# Sheet2.net
KiCad netlist of a schematic drawn in Altium Designer
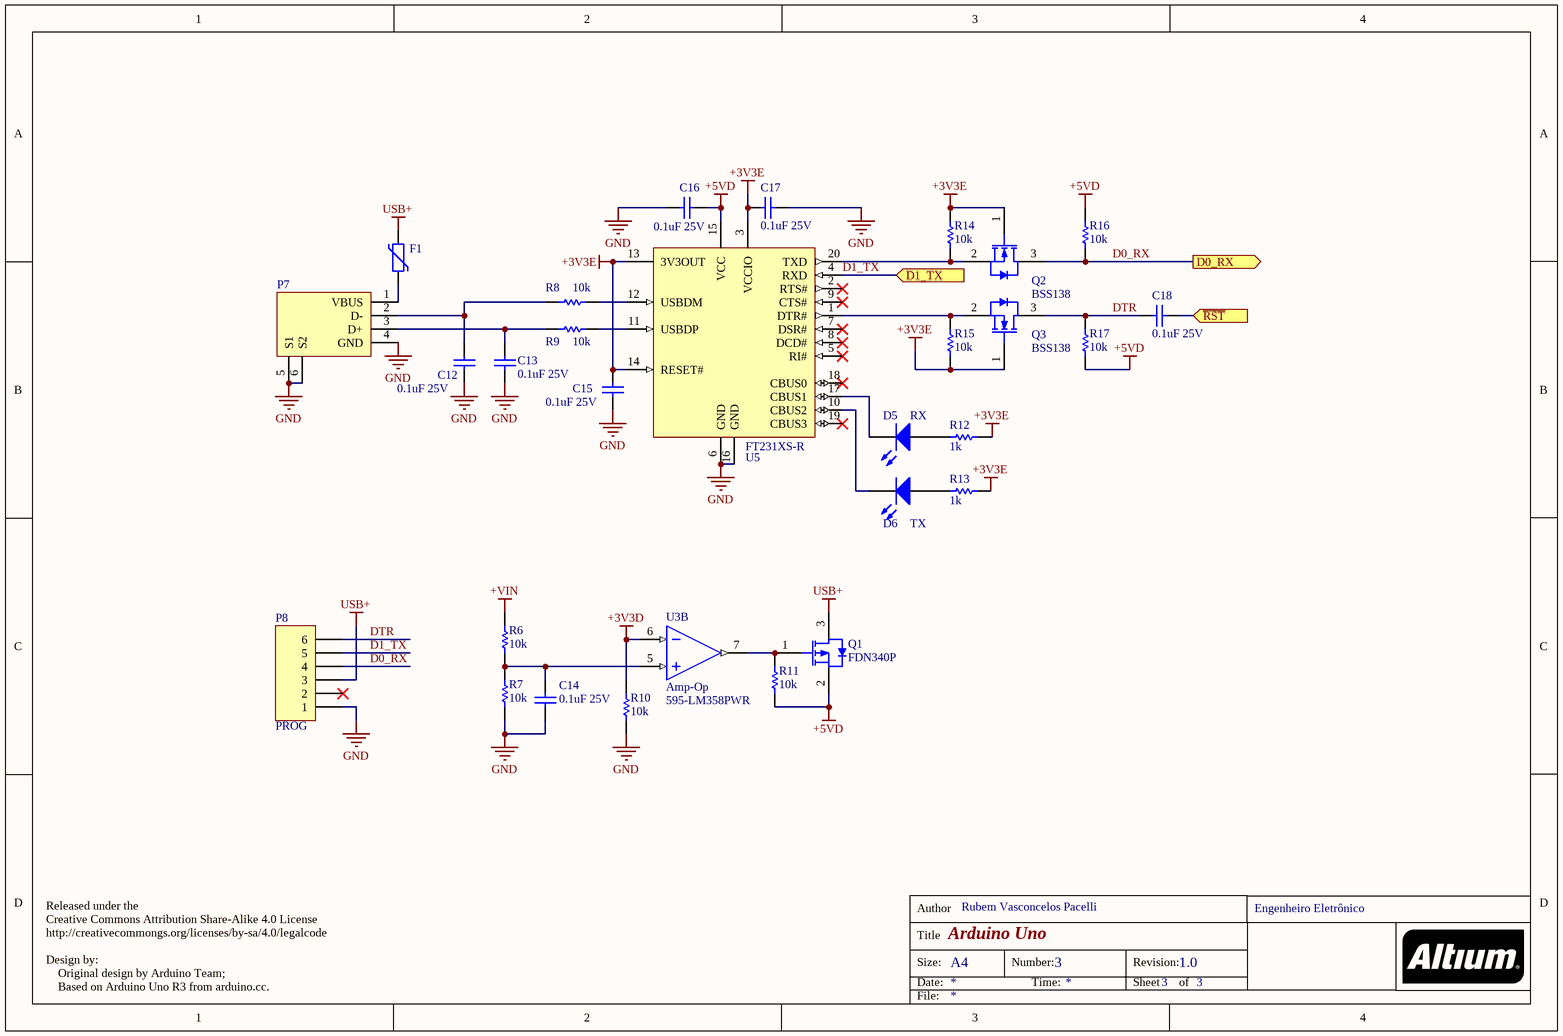
[diagram p0: Sheet2.SchDoc]

(export (version "E")
  (design (tool "Eeschema 10.0.6"))
  (components
    (comp (ref "C12")
      (value "0.1uF 25V")
      (footprint "C1608[0603]")
      (description "Capacitor Decoupling")
      (fields (field (name "MANUFACTURER PART NUMBER") "GCM188R71E104KA57D") (field (name "TOLERANCE") "10%"))
      (libsource (lib "Basic Library") (part "C"))
    )
    (comp (ref "C13")
      (value "0.1uF 25V")
      (footprint "C1608[0603]")
      (description "Capacitor Decoupling")
      (fields (field (name "MANUFACTURER PART NUMBER") "GCM188R71E104KA57D") (field (name "TOLERANCE") "10%"))
      (libsource (lib "Basic Library") (part "C"))
    )
    (comp (ref "C14")
      (value "0.1uF 25V")
      (footprint "C1608[0603]")
      (description "Decoupling Capacitor")
      (fields (field (name "MANUFACTURER PART NUMBER") "GCM188R71E104KA57D") (field (name "TOLERANCE") "10%"))
      (libsource (lib "Basic Library") (part "C"))
    )
    (comp (ref "C15")
      (value "0.1uF 25V")
      (footprint "C1608[0603]")
      (description "Capacitor Decoupling")
      (fields (field (name "MANUFACTURER PART NUMBER") "GCM188R71E104KA57D") (field (name "TOLERANCE") "10%"))
      (libsource (lib "Basic Library") (part "C"))
    )
    (comp (ref "C16")
      (value "0.1uF 25V")
      (footprint "C1608[0603]")
      (description "Capacitor Decoupling")
      (fields (field (name "MANUFACTURER PART NUMBER") "GCM188R71E104KA57D") (field (name "TOLERANCE") "10%"))
      (libsource (lib "Basic Library") (part "C"))
    )
    (comp (ref "C17")
      (value "0.1uF 25V")
      (footprint "C1608[0603]")
      (description "Capacitor Decoupling")
      (fields (field (name "MANUFACTURER PART NUMBER") "GCM188R71E104KA57D") (field (name "TOLERANCE") "10%"))
      (libsource (lib "Basic Library") (part "C"))
    )
    (comp (ref "C18")
      (value "0.1uF 25V")
      (footprint "C1608[0603]")
      (description "Capacitor Coupling")
      (fields (field (name "MANUFACTURER PART NUMBER") "GCM188R71E104KA57D") (field (name "TOLERANCE") "10%"))
      (libsource (lib "Basic Library") (part "C"))
    )
    (comp (ref "D5")
      (value "RX")
      (footprint "LED-0603-R")
      (description "LED visual indicator")
      (fields (field (name "MANUFACTURER PART NUMBER") "LTST-C190KSKT"))
      (libsource (lib "Basic Library") (part "LED"))
    )
    (comp (ref "D6")
      (value "TX")
      (footprint "LED-0603-R")
      (description "LED visual indicator")
      (fields (field (name "MANUFACTURER PART NUMBER") "LTST-C190KSKT"))
      (libsource (lib "Basic Library") (part "LED"))
    )
    (comp (ref "F1")
      (value "~")
      (footprint "MF-MSMF050")
      (description "Resettable Fuse")
      (fields (field (name "MANUFACTURER PART NUMBER") "MF-MSMF050-2"))
      (libsource (lib "Components Library") (part "MF-MSMF050-2"))
    )
    (comp (ref "P7")
      (value "~")
      (footprint "USBB1HSB6")
      (description "USB - B Receptacle")
      (fields
        (field (name "MANUFACTURER") "On-Shore Technology")
        (field (name "MANUFACTURER PART NUMBER") "USB-B1HSB6")
      )
      (libsource (lib "Connectors Library") (part "USB-B1HSB6"))
    )
    (comp (ref "P8")
      (value "PROG")
      (footprint "HDR1X6m")
      (description "Header, 6-Pin")
      (fields
        (field (name "MANUFACTURER") "Amphenol FCI")
        (field (name "MANUFACTURER PART NUMBER") "68000-406HLF")
        (field (name "PUBLISHER") "Altium Limited")
      )
      (libsource (lib "Connectors Library") (part "Header 6"))
    )
    (comp (ref "Q1")
      (value "FDN340P")
      (footprint "SOT23")
      (description "P-Channel MOSFET")
      (libsource (lib "Basic Library") (part "MOSFET-P"))
    )
    (comp (ref "Q2")
      (value "BSS138")
      (footprint "SOT23")
      (description "N-Channel MOSFET")
      (libsource (lib "Basic Library") (part "MOSFET-N"))
    )
    (comp (ref "Q3")
      (value "BSS138")
      (footprint "SOT23")
      (description "N-Channel MOSFET")
      (libsource (lib "Basic Library") (part "MOSFET-N"))
    )
    (comp (ref "R6")
      (value "10k")
      (footprint "R1608[0603]")
      (description "Resistor voltage divider")
      (fields (field (name "MANUFACTURER PART NUMBER") "MCT06030C1002FP500") (field (name "TOLERANCE") "1%"))
      (libsource (lib "Basic Library") (part "R"))
    )
    (comp (ref "R7")
      (value "10k")
      (footprint "R1608[0603]")
      (description "Resistor voltage divider")
      (fields (field (name "MANUFACTURER PART NUMBER") "MCT06030C1002FP500") (field (name "TOLERANCE") "1%"))
      (libsource (lib "Basic Library") (part "R"))
    )
    (comp (ref "R8")
      (value "10k")
      (footprint "R1608[0603]")
      (description "Resistor USB")
      (fields (field (name "MANUFACTURER PART NUMBER") "MCT06030C1002FP500") (field (name "TOLERANCE") "1%"))
      (libsource (lib "Basic Library") (part "R"))
    )
    (comp (ref "R9")
      (value "10k")
      (footprint "R1608[0603]")
      (description "Resistor USB")
      (fields (field (name "MANUFACTURER PART NUMBER") "MCT06030C1002FP500") (field (name "TOLERANCE") "1%"))
      (libsource (lib "Basic Library") (part "R"))
    )
    (comp (ref "R10")
      (value "10k")
      (footprint "R1608[0603]")
      (description "Resistor amp-op")
      (fields (field (name "MANUFACTURER PART NUMBER") "MCT06030C1002FP500") (field (name "TOLERANCE") "1%"))
      (libsource (lib "Basic Library") (part "R"))
    )
    (comp (ref "R11")
      (value "10k")
      (footprint "R1608[0603]")
      (description "Resistor MOSFET")
      (fields (field (name "MANUFACTURER PART NUMBER") "MCT06030C1002FP500") (field (name "TOLERANCE") "1%"))
      (libsource (lib "Basic Library") (part "R"))
    )
    (comp (ref "R12")
      (value "1k")
      (footprint "R1608[0603]")
      (description "Resistor LED")
      (fields (field (name "MANUFACTURER PART NUMBER") "ESR03EZPJ102") (field (name "TOLERANCE") "5%"))
      (libsource (lib "Basic Library") (part "R"))
    )
    (comp (ref "R13")
      (value "1k")
      (footprint "R1608[0603]")
      (description "Resistor LED")
      (fields (field (name "MANUFACTURER PART NUMBER") "ESR03EZPJ102") (field (name "TOLERANCE") "5%"))
      (libsource (lib "Basic Library") (part "R"))
    )
    (comp (ref "R14")
      (value "10k")
      (footprint "R1608[0603]")
      (description "Resistor MOSFET")
      (fields (field (name "MANUFACTURER PART NUMBER") "MCT06030C1002FP500") (field (name "TOLERANCE") "1%"))
      (libsource (lib "Basic Library") (part "R"))
    )
    (comp (ref "R15")
      (value "10k")
      (footprint "R1608[0603]")
      (description "Resistor MOSFET")
      (fields (field (name "MANUFACTURER PART NUMBER") "MCT06030C1002FP500") (field (name "TOLERANCE") "1%"))
      (libsource (lib "Basic Library") (part "R"))
    )
    (comp (ref "R16")
      (value "10k")
      (footprint "R1608[0603]")
      (description "Resistor pull-up")
      (fields (field (name "MANUFACTURER PART NUMBER") "MCT06030C1002FP500") (field (name "TOLERANCE") "1%"))
      (libsource (lib "Basic Library") (part "R"))
    )
    (comp (ref "R17")
      (value "10k")
      (footprint "R1608[0603]")
      (description "Resistor pull-up")
      (fields (field (name "MANUFACTURER PART NUMBER") "MCT06030C1002FP500") (field (name "TOLERANCE") "1%"))
      (libsource (lib "Basic Library") (part "R"))
    )
    (comp (ref "U3")
      (value "Amp-Op")
      (footprint "TSSOP8")
      (fields
        (field (name "MANUFACTURER") "Texas Instruments")
        (field (name "MANUFACTURER PART NUMBER") "LM358PWR")
        (field (name "SUPPLIER PART NUMBER 1") "595-LM358PWR")
      )
      (libsource (lib "Components Library") (part "LM358PWR"))
    )
    (comp (ref "U5")
      (value "FT231XS-R")
      (footprint "SSOP - 20")
      (fields (field (name "MANUFACTURER") "FTDI"))
      (libsource (lib "Components Library") (part "FT231XS-R"))
    )
  )
  (nets
    (net (code "1") (name "+3V3D") (class "Default")
      (node (ref "R10") (pin "1") (pinfunction "1_1") (pintype "passive"))
      (node (ref "U3") (pin "6") (pinfunction "IN2-_6") (pintype "input"))
    )
    (net (code "2") (name "+3V3E") (class "Default")
      (node (ref "C15") (pin "2") (pinfunction "2_2") (pintype "passive"))
      (node (ref "C17") (pin "2") (pinfunction "2_2") (pintype "passive"))
      (node (ref "Q2") (pin "1") (pinfunction "GATE_1") (pintype "passive"))
      (node (ref "Q3") (pin "1") (pinfunction "GATE_1") (pintype "passive"))
      (node (ref "R12") (pin "2") (pinfunction "2_2") (pintype "passive"))
      (node (ref "R13") (pin "2") (pinfunction "2_2") (pintype "passive"))
      (node (ref "R14") (pin "1") (pinfunction "1_1") (pintype "passive"))
      (node (ref "R15") (pin "2") (pinfunction "2_2") (pintype "passive"))
      (node (ref "U5") (pin "13") (pinfunction "3V3OUT_13") (pintype "power_in"))
      (node (ref "U5") (pin "14") (pinfunction "RESET#_14") (pintype "input"))
      (node (ref "U5") (pin "3") (pinfunction "VCCIO_3") (pintype "power_in"))
    )
    (net (code "3") (name "+5VD") (class "Default")
      (node (ref "C16") (pin "1") (pinfunction "1_1") (pintype "passive"))
      (node (ref "Q1") (pin "2") (pinfunction "SOURCE_2") (pintype "passive"))
      (node (ref "R11") (pin "2") (pinfunction "2_2") (pintype "passive"))
      (node (ref "R16") (pin "1") (pinfunction "1_1") (pintype "passive"))
      (node (ref "R17") (pin "2") (pinfunction "2_2") (pintype "passive"))
      (node (ref "U5") (pin "15") (pinfunction "VCC_15") (pintype "power_in"))
    )
    (net (code "4") (name "+VIN") (class "Default")
      (node (ref "R6") (pin "1") (pinfunction "1_1") (pintype "passive"))
    )
    (net (code "5") (name "/D0_RX") (class "Default")
      (node (ref "P8") (pin "4") (pinfunction "4_4") (pintype "passive"))
      (node (ref "Q2") (pin "3") (pinfunction "DRAIN_3") (pintype "passive"))
      (node (ref "R16") (pin "2") (pinfunction "2_2") (pintype "passive"))
    )
    (net (code "6") (name "/D1_TX") (class "Default")
      (node (ref "P8") (pin "5") (pinfunction "5_5") (pintype "passive"))
      (node (ref "U5") (pin "4") (pinfunction "RXD_4") (pintype "input"))
    )
    (net (code "7") (name "/DTR") (class "Default")
      (node (ref "C18") (pin "1") (pinfunction "1_1") (pintype "passive"))
      (node (ref "P8") (pin "6") (pinfunction "6_6") (pintype "passive"))
      (node (ref "Q3") (pin "3") (pinfunction "DRAIN_3") (pintype "passive"))
      (node (ref "R17") (pin "1") (pinfunction "1_1") (pintype "passive"))
    )
    (net (code "8") (name "/~{RST}") (class "Default")
      (node (ref "C18") (pin "2") (pinfunction "2_2") (pintype "passive"))
    )
    (net (code "9") (name "GND") (class "Default")
      (node (ref "C12") (pin "2") (pinfunction "2_2") (pintype "passive"))
      (node (ref "C13") (pin "2") (pinfunction "2_2") (pintype "passive"))
      (node (ref "C14") (pin "1") (pinfunction "1_1") (pintype "passive"))
      (node (ref "C15") (pin "1") (pinfunction "1_1") (pintype "passive"))
      (node (ref "C16") (pin "2") (pinfunction "2_2") (pintype "passive"))
      (node (ref "C17") (pin "1") (pinfunction "1_1") (pintype "passive"))
      (node (ref "P7") (pin "4") (pinfunction "GND_4") (pintype "passive"))
      (node (ref "P7") (pin "5") (pinfunction "S1_5") (pintype "passive"))
      (node (ref "P7") (pin "6") (pinfunction "S2_6") (pintype "passive"))
      (node (ref "P8") (pin "1") (pinfunction "1_1") (pintype "passive"))
      (node (ref "R10") (pin "2") (pinfunction "2_2") (pintype "passive"))
      (node (ref "R7") (pin "2") (pinfunction "2_2") (pintype "passive"))
      (node (ref "U5") (pin "16") (pinfunction "GND_16") (pintype "power_in"))
      (node (ref "U5") (pin "6") (pinfunction "GND_6") (pintype "power_in"))
    )
    (net (code "10") (name "Net-(D5-A)") (class "Default")
      (node (ref "D5") (pin "1") (pinfunction "A_1") (pintype "passive"))
      (node (ref "R12") (pin "1") (pinfunction "1_1") (pintype "passive"))
    )
    (net (code "11") (name "Net-(D5-K)") (class "Default")
      (node (ref "D5") (pin "2") (pinfunction "K_2") (pintype "passive"))
      (node (ref "U5") (pin "17") (pinfunction "CBUS1_17") (pintype "bidirectional"))
    )
    (net (code "12") (name "Net-(D6-A)") (class "Default")
      (node (ref "D6") (pin "1") (pinfunction "A_1") (pintype "passive"))
      (node (ref "R13") (pin "1") (pinfunction "1_1") (pintype "passive"))
    )
    (net (code "13") (name "Net-(D6-K)") (class "Default")
      (node (ref "D6") (pin "2") (pinfunction "K_2") (pintype "passive"))
      (node (ref "U5") (pin "10") (pinfunction "CBUS2_10") (pintype "bidirectional"))
    )
    (net (code "14") (name "Net-(P7-D+)") (class "Default")
      (node (ref "C13") (pin "1") (pinfunction "1_1") (pintype "passive"))
      (node (ref "P7") (pin "3") (pinfunction "D+_3") (pintype "passive"))
      (node (ref "R9") (pin "2") (pinfunction "2_2") (pintype "passive"))
    )
    (net (code "15") (name "Net-(P7-D-)") (class "Default")
      (node (ref "C12") (pin "1") (pinfunction "1_1") (pintype "passive"))
      (node (ref "P7") (pin "2") (pinfunction "D-_2") (pintype "passive"))
      (node (ref "R8") (pin "2") (pinfunction "2_2") (pintype "passive"))
    )
    (net (code "16") (name "Net-(P7-VBUS)") (class "Default")
      (node (ref "F1") (pin "1") (pinfunction "1_1") (pintype "passive"))
      (node (ref "P7") (pin "1") (pinfunction "VBUS_1") (pintype "passive"))
    )
    (net (code "17") (name "Net-(Q1-GATE)") (class "Default")
      (node (ref "Q1") (pin "1") (pinfunction "GATE_1") (pintype "passive"))
      (node (ref "R11") (pin "1") (pinfunction "1_1") (pintype "passive"))
      (node (ref "U3") (pin "7") (pinfunction "OUT2_7") (pintype "output"))
    )
    (net (code "18") (name "Net-(Q2-SOURCE)") (class "Default")
      (node (ref "Q2") (pin "2") (pinfunction "SOURCE_2") (pintype "passive"))
      (node (ref "R14") (pin "2") (pinfunction "2_2") (pintype "passive"))
      (node (ref "U5") (pin "20") (pinfunction "TXD_20") (pintype "output"))
    )
    (net (code "19") (name "Net-(Q3-SOURCE)") (class "Default")
      (node (ref "Q3") (pin "2") (pinfunction "SOURCE_2") (pintype "passive"))
      (node (ref "R15") (pin "1") (pinfunction "1_1") (pintype "passive"))
      (node (ref "U5") (pin "1") (pinfunction "DTR#_1") (pintype "output"))
    )
    (net (code "20") (name "Net-(U3B-IN2+)") (class "Default")
      (node (ref "C14") (pin "2") (pinfunction "2_2") (pintype "passive"))
      (node (ref "R6") (pin "2") (pinfunction "2_2") (pintype "passive"))
      (node (ref "R7") (pin "1") (pinfunction "1_1") (pintype "passive"))
      (node (ref "U3") (pin "5") (pinfunction "IN2+_5") (pintype "input"))
    )
    (net (code "21") (name "Net-(U5-USBDM)") (class "Default")
      (node (ref "R8") (pin "1") (pinfunction "1_1") (pintype "passive"))
      (node (ref "U5") (pin "12") (pinfunction "USBDM_12") (pintype "input"))
    )
    (net (code "22") (name "Net-(U5-USBDP)") (class "Default")
      (node (ref "R9") (pin "1") (pinfunction "1_1") (pintype "passive"))
      (node (ref "U5") (pin "11") (pinfunction "USBDP_11") (pintype "input"))
    )
    (net (code "23") (name "USB+") (class "Default")
      (node (ref "F1") (pin "2") (pinfunction "2_2") (pintype "passive"))
      (node (ref "P8") (pin "3") (pinfunction "3_3") (pintype "passive"))
      (node (ref "Q1") (pin "3") (pinfunction "DRAIN_3") (pintype "passive"))
    )
    (net (code "24") (name "unconnected-(P8-Pad2)") (class "Default")
      (node (ref "P8") (pin "2") (pinfunction "2_2") (pintype "passive+no_connect"))
    )
    (net (code "25") (name "unconnected-(U5-CBUS0-Pad18)") (class "Default")
      (node (ref "U5") (pin "18") (pinfunction "CBUS0_18") (pintype "bidirectional+no_connect"))
    )
    (net (code "26") (name "unconnected-(U5-CBUS3-Pad19)") (class "Default")
      (node (ref "U5") (pin "19") (pinfunction "CBUS3_19") (pintype "bidirectional+no_connect"))
    )
    (net (code "27") (name "unconnected-(U5-CTS#-Pad9)") (class "Default")
      (node (ref "U5") (pin "9") (pinfunction "CTS#_9") (pintype "input+no_connect"))
    )
    (net (code "28") (name "unconnected-(U5-DCD#-Pad8)") (class "Default")
      (node (ref "U5") (pin "8") (pinfunction "DCD#_8") (pintype "input+no_connect"))
    )
    (net (code "29") (name "unconnected-(U5-DSR#-Pad7)") (class "Default")
      (node (ref "U5") (pin "7") (pinfunction "DSR#_7") (pintype "input+no_connect"))
    )
    (net (code "30") (name "unconnected-(U5-RI#-Pad5)") (class "Default")
      (node (ref "U5") (pin "5") (pinfunction "RI#_5") (pintype "input+no_connect"))
    )
    (net (code "31") (name "unconnected-(U5-RTS#-Pad2)") (class "Default")
      (node (ref "U5") (pin "2") (pinfunction "RTS#_2") (pintype "output+no_connect"))
    )
  )
)
